# etap2.net
KiCad netlist of a schematic drawn in Altium Designer
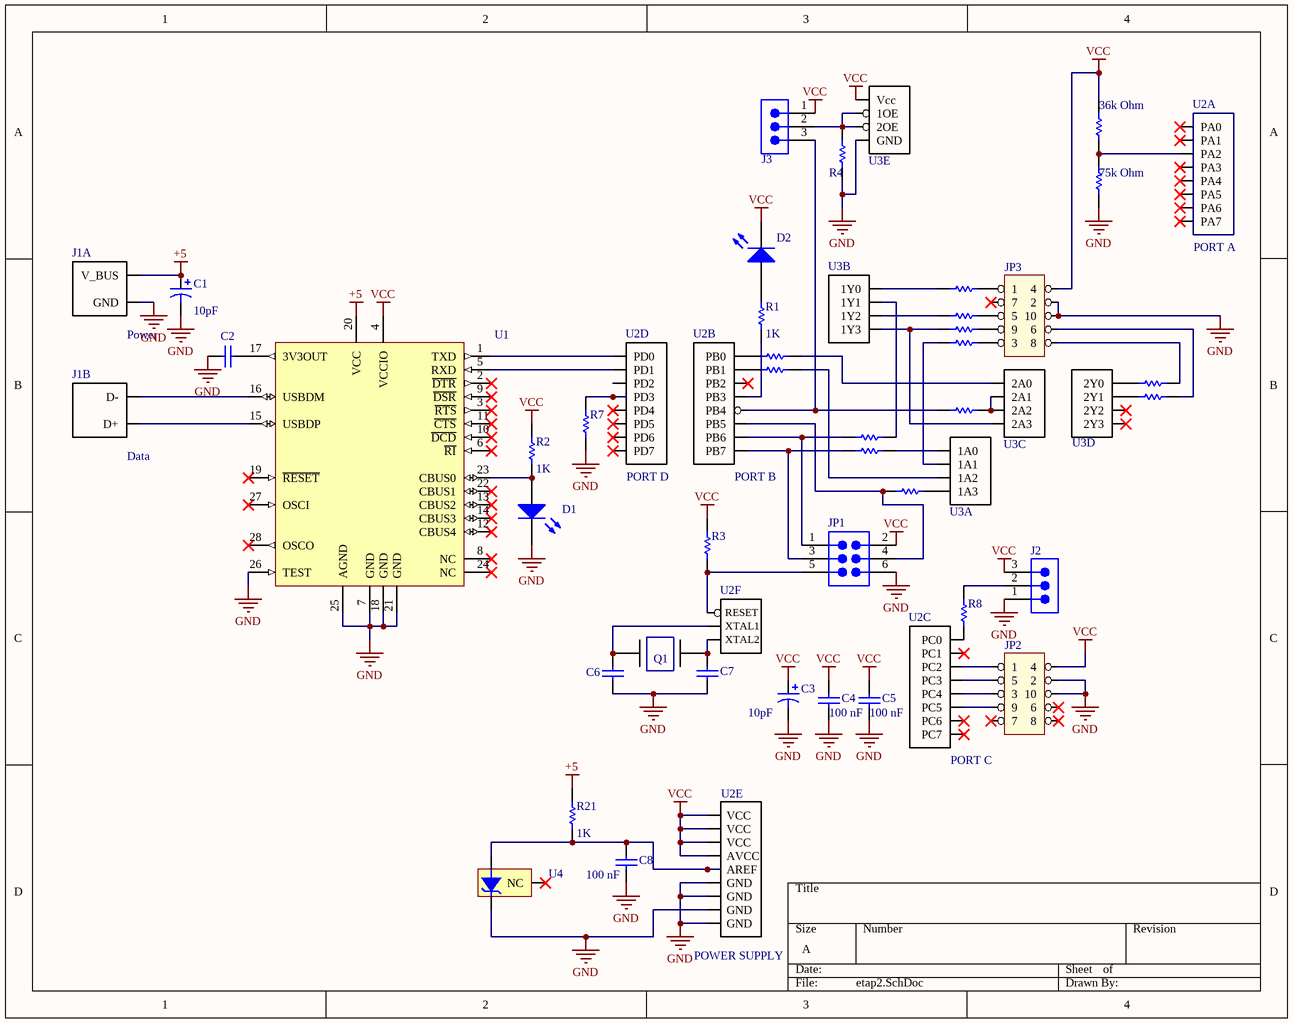
[diagram p0: etap2.SchDoc]

(export (version "E")
  (design (tool "Eeschema 10.0.6"))
  (components
    (comp (ref "C1")
      (value "10pF")
      (footprint "RB7.6-15")
      (description "Polarized Capacitor (Radial)")
      (fields (field (name "Comment") "Cap Pol1") (field (name "PUBLISHER") "Altium Limited"))
      (libsource (lib "Miscellaneous Devices") (part "Cap Pol1"))
    )
    (comp (ref "C2")
      (value "06035C104KAT2A")
      (footprint "CAPC1608X90X35LL15T15")
      (description "Chip Capacitor, 100 nF, +/- 10%, 50 V, -55 to 125 degC, 0603 (1608 Metric), RoHS, Tape and Reel")
      (fields (field (name "TOLERANCE") "10%"))
      (libsource (lib "Altium Content Vault") (part "CMP-2006-04389-2"))
    )
    (comp (ref "C3")
      (value "10pF")
      (footprint "RB7.6-15")
      (description "Polarized Capacitor (Radial)")
      (fields (field (name "Comment") "Cap Pol1") (field (name "PUBLISHER") "Altium Limited"))
      (libsource (lib "Miscellaneous Devices") (part "Cap Pol1"))
    )
    (comp (ref "C4")
      (value "06035C104KAT2A")
      (footprint "CAPC1608X90X35LL15T15")
      (description "Chip Capacitor, 100 nF, +/- 10%, 50 V, -55 to 125 degC, 0603 (1608 Metric), RoHS, Tape and Reel")
      (fields (field (name "CAPACITANCE") "100 nF") (field (name "TOLERANCE") "10%"))
      (libsource (lib "Altium Content Vault") (part "CMP-2006-04389-2"))
    )
    (comp (ref "C5")
      (value "06035C104KAT2A")
      (footprint "CAPC1608X90X35LL15T15")
      (description "Chip Capacitor, 100 nF, +/- 10%, 50 V, -55 to 125 degC, 0603 (1608 Metric), RoHS, Tape and Reel")
      (fields (field (name "CAPACITANCE") "100 nF") (field (name "TOLERANCE") "10%"))
      (libsource (lib "Altium Content Vault") (part "CMP-2006-04389-2"))
    )
    (comp (ref "C6")
      (value "CAP 22pF 50V 0402(1005)")
      (footprint "CAPC0402(1005)60_L")
      (description "CAP 22pF 50V ±0.5pF 0402 (1005 Metric) Thickness 0.6mm SMD")
      (fields (field (name "TOLERANCE") "Â±0.5pF"))
      (libsource (lib "Altium Content Vault") (part "CMP-1034-00913-1"))
    )
    (comp (ref "C7")
      (value "CAP 22pF 50V 0402(1005)")
      (footprint "CAPC0402(1005)60_L")
      (description "CAP 22pF 50V ±0.5pF 0402 (1005 Metric) Thickness 0.6mm SMD")
      (fields (field (name "TOLERANCE") "Â±0.5pF"))
      (libsource (lib "Altium Content Vault") (part "CMP-1034-00913-1"))
    )
    (comp (ref "C8")
      (value "06035C104KAT2A")
      (footprint "CAPC1608X90X35LL15T15")
      (description "Chip Capacitor, 100 nF, +/- 10%, 50 V, -55 to 125 degC, 0603 (1608 Metric), RoHS, Tape and Reel")
      (fields (field (name "CAPACITANCE") "100 nF") (field (name "TOLERANCE") "10%"))
      (libsource (lib "Altium Content Vault") (part "CMP-2006-04389-2"))
    )
    (comp (ref "D1")
      (value "151033YS03000")
      (footprint "Type 3mm")
      (description "THT LED round mono-color waterclear, WL-TMRW, Yellow")
      (fields (field (name "MANUFACTURER") "Wuerth Elektronik"))
      (libsource (lib "Altium Content Vault") (part "CMP-1489-00003-1"))
    )
    (comp (ref "D2")
      (value "151033GS03000")
      (footprint "Type 3mm")
      (description "THT LED round mono-color waterclear, THT WL-TMRW ,Green")
      (fields (field (name "MANUFACTURER") "Wuerth Elektronik"))
      (libsource (lib "Altium Content Vault") (part "CMP-1489-00001-1"))
    )
    (comp (ref "J1")
      (value "USB-B-S-X-X-TH")
      (footprint "USB_B")
      (description "USB-B interface")
      (libsource (lib "etap1") (part "USB-B-S-X-X-TH"))
    )
    (comp (ref "J2")
      (value "BG055-03-A-1-0650-0530-0350-L-B")
      (footprint "GCT-BG055-03-A-1-0650-0530-0350_V")
      (fields (field (name "MANUFACTURER") "GCT"))
      (libsource (lib "Altium Content Vault") (part "CMP-0815-00002-1"))
    )
    (comp (ref "J3")
      (value "BG055-03-A-1-0650-0530-0350-L-B")
      (footprint "GCT-BG055-03-A-1-0650-0530-0350_V")
      (fields (field (name "MANUFACTURER") "GCT"))
      (libsource (lib "") (part "CMP-0815-00002-1_1"))
    )
    (comp (ref "JP1")
      (value "TSW-103-08-G-D")
      (footprint "SMTC-TSW-103-08-X-D")
      (fields (field (name "MANUFACTURER") "Samtec"))
      (libsource (lib "Altium Content Vault") (part "CMP-1024-00338-1"))
    )
    (comp (ref "JP2") (value "IDC male 2.54 connector") (libsource (lib "etap1") (part "ZL231-10PG")))
    (comp (ref "JP3") (value "IDC male 2.54 connector") (libsource (lib "etap1") (part "ZL231-10GK")))
    (comp (ref "Q1") (value "XTAL") (libsource (lib "etap1") (part "HC49US-FF3F18")))
    (comp (ref "R1")
      (value "1K")
      (footprint "AXIAL-0.3")
      (description "Resistor")
      (fields (field (name "Comment") "Res1") (field (name "PUBLISHER") "Altium Limited"))
      (libsource (lib "Miscellaneous Devices") (part "Res1"))
    )
    (comp (ref "R2")
      (value "1K")
      (footprint "AXIAL-0.3")
      (description "Resistor")
      (fields (field (name "Comment") "Res1") (field (name "PUBLISHER") "Altium Limited"))
      (libsource (lib "Miscellaneous Devices") (part "Res1"))
    )
    (comp (ref "R3")
      (value "10K 1% 1812(4532)")
      (footprint "RESC1812(4532)_L")
      (description "10K 0.75W 1% 1812 (4532 Metric)  SMD")
      (fields (field (name "POWER") "0.75 W") (field (name "TOLERANCE") "1 %"))
      (libsource (lib "Altium Content Vault") (part "CMP-1016-00602-1"))
    )
    (comp (ref "R4")
      (value "10K 1% 1812(4532)")
      (footprint "RESC1812(4532)_L")
      (description "10K 0.75W 1% 1812 (4532 Metric)  SMD")
      (fields (field (name "POWER") "0.75 W") (field (name "TOLERANCE") "1 %"))
      (libsource (lib "Altium Content Vault") (part "CMP-1016-00602-1"))
    )
    (comp (ref "R5")
      (value "36k Ohm")
      (footprint "RESC0201(0603)_L")
      (description "36K 0.05W 5% 0201 (0603 Metric)  SMD")
      (fields (field (name "POWER") "0.05 W") (field (name "TOLERANCE") "5 %"))
      (libsource (lib "Altium Content Vault") (part "CMP-1010-00111-1"))
    )
    (comp (ref "R6")
      (value "75k Ohm")
      (footprint "RESC2010(5025)_M")
      (description "75K 0.75W 1% 2010 (5025 Metric)  SMD")
      (fields (field (name "TOLERANCE") "1 %") (field (name "POWER") "0.75 W"))
      (libsource (lib "Altium Content Vault") (part "CMP-1017-00722-1"))
    )
    (comp (ref "R7")
      (value "10K 1% 1812(4532)")
      (footprint "RESC1812(4532)_L")
      (description "10K 0.75W 1% 1812 (4532 Metric)  SMD")
      (fields (field (name "POWER") "0.75 W") (field (name "TOLERANCE") "1 %"))
      (libsource (lib "Altium Content Vault") (part "CMP-1016-00602-1"))
    )
    (comp (ref "R8")
      (value "Res1")
      (footprint "AXIAL-0.3")
      (description "Resistor")
      (fields (field (name "PUBLISHER") "Altium Limited"))
      (libsource (lib "Miscellaneous Devices") (part "Res1"))
    )
    (comp (ref "R9")
      (value "Res1")
      (footprint "AXIAL-0.3")
      (description "Resistor")
      (fields (field (name "PUBLISHER") "Altium Limited"))
      (libsource (lib "Miscellaneous Devices") (part "Res1"))
    )
    (comp (ref "R10")
      (value "Res1")
      (footprint "AXIAL-0.3")
      (description "Resistor")
      (fields (field (name "PUBLISHER") "Altium Limited"))
      (libsource (lib "Miscellaneous Devices") (part "Res1"))
    )
    (comp (ref "R11")
      (value "Res1")
      (footprint "AXIAL-0.3")
      (description "Resistor")
      (fields (field (name "PUBLISHER") "Altium Limited"))
      (libsource (lib "Miscellaneous Devices") (part "Res1"))
    )
    (comp (ref "R12")
      (value "Res1")
      (footprint "AXIAL-0.3")
      (description "Resistor")
      (fields (field (name "PUBLISHER") "Altium Limited"))
      (libsource (lib "Miscellaneous Devices") (part "Res1"))
    )
    (comp (ref "R13")
      (value "Res1")
      (footprint "AXIAL-0.3")
      (description "Resistor")
      (fields (field (name "PUBLISHER") "Altium Limited"))
      (libsource (lib "Miscellaneous Devices") (part "Res1"))
    )
    (comp (ref "R14")
      (value "Res1")
      (footprint "AXIAL-0.3")
      (description "Resistor")
      (fields (field (name "PUBLISHER") "Altium Limited"))
      (libsource (lib "Miscellaneous Devices") (part "Res1"))
    )
    (comp (ref "R15")
      (value "Res1")
      (footprint "AXIAL-0.3")
      (description "Resistor")
      (fields (field (name "PUBLISHER") "Altium Limited"))
      (libsource (lib "Miscellaneous Devices") (part "Res1"))
    )
    (comp (ref "R16")
      (value "100R 1% 2512(6432)")
      (footprint "RESC2512(6432)_N")
      (description "100R 1W 1% 2512 (6432 Metric)  SMD")
      (fields (field (name "POWER") "1 W") (field (name "TOLERANCE") "1 %"))
      (libsource (lib "Altium Content Vault") (part "CMP-1018-00397-1"))
    )
    (comp (ref "R17")
      (value "100R 1% 2512(6432)")
      (footprint "RESC2512(6432)_N")
      (description "100R 1W 1% 2512 (6432 Metric)  SMD")
      (fields (field (name "POWER") "1 W") (field (name "TOLERANCE") "1 %"))
      (libsource (lib "Altium Content Vault") (part "CMP-1018-00397-1"))
    )
    (comp (ref "R18")
      (value "100R 1% 2512(6432)")
      (footprint "RESC2512(6432)_N")
      (description "100R 1W 1% 2512 (6432 Metric)  SMD")
      (fields (field (name "POWER") "1 W") (field (name "TOLERANCE") "1 %"))
      (libsource (lib "Altium Content Vault") (part "CMP-1018-00397-1"))
    )
    (comp (ref "R19")
      (value "Res1")
      (footprint "AXIAL-0.3")
      (description "Resistor")
      (fields (field (name "PUBLISHER") "Altium Limited"))
      (libsource (lib "Miscellaneous Devices") (part "Res1"))
    )
    (comp (ref "R20")
      (value "Res1")
      (footprint "AXIAL-0.3")
      (description "Resistor")
      (fields (field (name "PUBLISHER") "Altium Limited"))
      (libsource (lib "Miscellaneous Devices") (part "Res1"))
    )
    (comp (ref "R21")
      (value "1K")
      (footprint "AXIAL-0.3")
      (description "Resistor")
      (fields (field (name "Comment") "Res1") (field (name "PUBLISHER") "Altium Limited"))
      (libsource (lib "Miscellaneous Devices") (part "Res1"))
    )
    (comp (ref "U1")
      (value "FT232RL-Reel")
      (footprint "SSOP-28_L")
      (description "USB UART Asynchronous Serial Data Transfer Chip, 28-pin SSOP, Tape and Reel")
      (fields (field (name "MANUFACTURER") "FTDI"))
      (libsource (lib "Altium Content Vault") (part "CMP-0078-00029-3"))
    )
    (comp (ref "U2")
      (value "Microcontroller")
      (footprint "TQFP44")
      (description "Microcontroller with 16k bytes in-system programmable flash")
      (libsource (lib "etap1") (part "Atmega16-16AU"))
    )
    (comp (ref "U3") (value "Octal buffer-line driver") (libsource (lib "etap1") (part "74HC2444N")))
    (comp (ref "U4")
      (value "LM385BYZ-2.5")
      (footprint "Z03A")
      (description "Micropower Voltage Reference Diode, 3-pin TO-92")
      (fields (field (name "MANUFACTURER") "National Semiconductor"))
      (libsource (lib "Altium Content Vault") (part "CMP-0074-00031-2"))
    )
  )
  (nets
    (net (code "1") (name "+5") (class "Default")
      (node (ref "C1") (pin "1") (pinfunction "1_1") (pintype "passive"))
      (node (ref "J1") (pin "1") (pinfunction "V_BUS_1") (pintype "passive"))
      (node (ref "R21") (pin "2") (pinfunction "2_2") (pintype "passive"))
      (node (ref "U1") (pin "20") (pinfunction "VCC_20") (pintype "power_in"))
    )
    (net (code "2") (name "GND") (class "Default")
      (node (ref "C1") (pin "2") (pinfunction "2_2") (pintype "passive"))
      (node (ref "C2") (pin "2") (pinfunction "2_2") (pintype "passive"))
      (node (ref "C3") (pin "2") (pinfunction "2_2") (pintype "passive"))
      (node (ref "C4") (pin "1") (pinfunction "1_1") (pintype "passive"))
      (node (ref "C5") (pin "1") (pinfunction "1_1") (pintype "passive"))
      (node (ref "C6") (pin "1") (pinfunction "1_1") (pintype "passive"))
      (node (ref "C7") (pin "1") (pinfunction "1_1") (pintype "passive"))
      (node (ref "C8") (pin "1") (pinfunction "1_1") (pintype "passive"))
      (node (ref "D1") (pin "1") (pinfunction "K_1") (pintype "passive"))
      (node (ref "J1") (pin "4") (pinfunction "GND_4") (pintype "passive"))
      (node (ref "J2") (pin "1") (pinfunction "1_1") (pintype "passive"))
      (node (ref "JP1") (pin "6") (pinfunction "6_6") (pintype "passive"))
      (node (ref "JP2") (pin "10") (pinfunction "10_10") (pintype "passive"))
      (node (ref "JP2") (pin "2") (pinfunction "2_2") (pintype "passive"))
      (node (ref "JP3") (pin "10") (pinfunction "10_10") (pintype "passive"))
      (node (ref "JP3") (pin "2") (pinfunction "2_2") (pintype "passive"))
      (node (ref "R4") (pin "1") (pinfunction "1_1") (pintype "passive"))
      (node (ref "R6") (pin "1") (pinfunction "1_1") (pintype "passive"))
      (node (ref "R7") (pin "1") (pinfunction "1_1") (pintype "passive"))
      (node (ref "U1") (pin "18") (pinfunction "GND_18") (pintype "power_in"))
      (node (ref "U1") (pin "21") (pinfunction "GND_21") (pintype "power_in"))
      (node (ref "U1") (pin "25") (pinfunction "AGND_25") (pintype "power_in"))
      (node (ref "U1") (pin "26") (pinfunction "TEST_26") (pintype "input"))
      (node (ref "U1") (pin "7") (pinfunction "GND_7") (pintype "power_in"))
      (node (ref "U2") (pin "18") (pinfunction "GND_18") (pintype "passive"))
      (node (ref "U2") (pin "28") (pinfunction "GND_28") (pintype "passive"))
      (node (ref "U2") (pin "39") (pinfunction "GND_39") (pintype "passive"))
      (node (ref "U2") (pin "6") (pinfunction "GND_6") (pintype "passive"))
      (node (ref "U3") (pin "10") (pinfunction "GND_10") (pintype "passive"))
      (node (ref "U4") (pin "2") (pinfunction "+V_2") (pintype "passive"))
    )
    (net (code "3") (name "Net-(D1-A)") (class "Default")
      (node (ref "D1") (pin "2") (pinfunction "A_2") (pintype "passive"))
      (node (ref "R2") (pin "1") (pinfunction "1_1") (pintype "passive"))
      (node (ref "U1") (pin "23") (pinfunction "CBUS0_23") (pintype "bidirectional"))
    )
    (net (code "4") (name "Net-(D2-A)") (class "Default")
      (node (ref "D2") (pin "2") (pinfunction "A_2") (pintype "passive"))
      (node (ref "R1") (pin "2") (pinfunction "2_2") (pintype "passive"))
    )
    (net (code "5") (name "Net-(J1B-D+)") (class "Default")
      (node (ref "J1") (pin "3") (pinfunction "D+_3") (pintype "passive"))
      (node (ref "U1") (pin "15") (pinfunction "USBDP_15") (pintype "bidirectional"))
    )
    (net (code "6") (name "Net-(J1B-D-)") (class "Default")
      (node (ref "J1") (pin "2") (pinfunction "D-_2") (pintype "passive"))
      (node (ref "U1") (pin "16") (pinfunction "USBDM_16") (pintype "bidirectional"))
    )
    (net (code "7") (name "Net-(J2-Pad2)") (class "Default")
      (node (ref "J2") (pin "2") (pinfunction "2_2") (pintype "passive"))
      (node (ref "R8") (pin "2") (pinfunction "2_2") (pintype "passive"))
    )
    (net (code "8") (name "Net-(JP3-Pad1)") (class "Default")
      (node (ref "JP3") (pin "1") (pinfunction "1_1") (pintype "passive"))
      (node (ref "R16") (pin "2") (pinfunction "2_2") (pintype "passive"))
    )
    (net (code "9") (name "Net-(JP3-Pad3)") (class "Default")
      (node (ref "JP3") (pin "3") (pinfunction "3_3") (pintype "passive"))
      (node (ref "R15") (pin "1") (pinfunction "1_1") (pintype "passive"))
    )
    (net (code "10") (name "Net-(JP3-Pad5)") (class "Default")
      (node (ref "JP3") (pin "5") (pinfunction "5_5") (pintype "passive"))
      (node (ref "R17") (pin "2") (pinfunction "2_2") (pintype "passive"))
    )
    (net (code "11") (name "Net-(JP3-Pad6)") (class "Default")
      (node (ref "JP3") (pin "6") (pinfunction "6_6") (pintype "passive"))
      (node (ref "R20") (pin "1") (pinfunction "1_1") (pintype "passive"))
    )
    (net (code "12") (name "Net-(JP3-Pad8)") (class "Default")
      (node (ref "JP3") (pin "8") (pinfunction "8_8") (pintype "passive"))
      (node (ref "R19") (pin "2") (pinfunction "2_2") (pintype "passive"))
    )
    (net (code "13") (name "Net-(JP3-Pad9)") (class "Default")
      (node (ref "JP3") (pin "9") (pinfunction "9_9") (pintype "passive"))
      (node (ref "R18") (pin "2") (pinfunction "2_2") (pintype "passive"))
    )
    (net (code "14") (name "Net-(U1-3V3OUT)") (class "Default")
      (node (ref "C2") (pin "1") (pinfunction "1_1") (pintype "passive"))
      (node (ref "U1") (pin "17") (pinfunction "3V3OUT_17") (pintype "output"))
    )
    (net (code "15") (name "Net-(U1-RXD)") (class "Default")
      (node (ref "U1") (pin "5") (pinfunction "RXD_5") (pintype "input"))
      (node (ref "U2") (pin "10") (pinfunction "PD1_10") (pintype "passive"))
    )
    (net (code "16") (name "Net-(U1-TXD)") (class "Default")
      (node (ref "U1") (pin "1") (pinfunction "TXD_1") (pintype "output"))
      (node (ref "U2") (pin "9") (pinfunction "PD0_9") (pintype "passive"))
    )
    (net (code "17") (name "Net-(U2A-PA2)") (class "Default")
      (node (ref "R5") (pin "1") (pinfunction "1_1") (pintype "passive"))
      (node (ref "R6") (pin "2") (pinfunction "2_2") (pintype "passive"))
      (node (ref "U2") (pin "35") (pinfunction "PA2_35") (pintype "passive"))
    )
    (net (code "18") (name "Net-(U2B-PB0)") (class "Default")
      (node (ref "R13") (pin "2") (pinfunction "2_2") (pintype "passive"))
      (node (ref "U2") (pin "40") (pinfunction "PB0_40") (pintype "passive"))
    )
    (net (code "19") (name "Net-(U2B-PB1)") (class "Default")
      (node (ref "R11") (pin "2") (pinfunction "2_2") (pintype "passive"))
      (node (ref "U2") (pin "41") (pinfunction "PB1_41") (pintype "passive"))
    )
    (net (code "20") (name "Net-(U2B-PB3)") (class "Default")
      (node (ref "R1") (pin "1") (pinfunction "1_1") (pintype "passive"))
      (node (ref "U2") (pin "43") (pinfunction "PB3_43") (pintype "passive"))
    )
    (net (code "21") (name "Net-(U2B-PB4)") (class "Default")
      (node (ref "J3") (pin "3") (pinfunction "3_3") (pintype "passive"))
      (node (ref "R14") (pin "2") (pinfunction "2_2") (pintype "passive"))
      (node (ref "U2") (pin "44") (pinfunction "PB4_44") (pintype "passive"))
    )
    (net (code "22") (name "Net-(U2B-PB5)") (class "Default")
      (node (ref "JP1") (pin "4") (pinfunction "4_4") (pintype "passive"))
      (node (ref "R12") (pin "2") (pinfunction "2_2") (pintype "passive"))
      (node (ref "U2") (pin "1") (pinfunction "PB5_1") (pintype "passive"))
    )
    (net (code "23") (name "Net-(U2B-PB6)") (class "Default")
      (node (ref "JP1") (pin "1") (pinfunction "1_1") (pintype "passive"))
      (node (ref "R9") (pin "2") (pinfunction "2_2") (pintype "passive"))
      (node (ref "U2") (pin "2") (pinfunction "PB6_2") (pintype "passive"))
    )
    (net (code "24") (name "Net-(U2B-PB7)") (class "Default")
      (node (ref "JP1") (pin "3") (pinfunction "3_3") (pintype "passive"))
      (node (ref "R10") (pin "2") (pinfunction "2_2") (pintype "passive"))
      (node (ref "U2") (pin "3") (pinfunction "PB7_3") (pintype "passive"))
    )
    (net (code "25") (name "Net-(U2C-PC0)") (class "Default")
      (node (ref "R8") (pin "1") (pinfunction "1_1") (pintype "passive"))
      (node (ref "U2") (pin "19") (pinfunction "PC0_19") (pintype "passive"))
    )
    (net (code "26") (name "Net-(U2C-PC2)") (class "Default")
      (node (ref "JP2") (pin "1") (pinfunction "1_1") (pintype "passive"))
      (node (ref "U2") (pin "21") (pinfunction "PC2_21") (pintype "passive"))
    )
    (net (code "27") (name "Net-(U2C-PC3)") (class "Default")
      (node (ref "JP2") (pin "5") (pinfunction "5_5") (pintype "passive"))
      (node (ref "U2") (pin "22") (pinfunction "PC3_22") (pintype "passive"))
    )
    (net (code "28") (name "Net-(U2C-PC4)") (class "Default")
      (node (ref "JP2") (pin "3") (pinfunction "3_3") (pintype "passive"))
      (node (ref "U2") (pin "23") (pinfunction "PC4_23") (pintype "passive"))
    )
    (net (code "29") (name "Net-(U2C-PC5)") (class "Default")
      (node (ref "JP2") (pin "9") (pinfunction "9_9") (pintype "passive"))
      (node (ref "U2") (pin "24") (pinfunction "PC5_24") (pintype "passive"))
    )
    (net (code "30") (name "Net-(U2D-PD3)") (class "Default")
      (node (ref "R7") (pin "2") (pinfunction "2_2") (pintype "passive"))
      (node (ref "U2") (pin "12") (pinfunction "PD3_12") (pintype "passive"))
    )
    (net (code "31") (name "Net-(U2E-AREF)") (class "Default")
      (node (ref "C8") (pin "2") (pinfunction "2_2") (pintype "passive"))
      (node (ref "R21") (pin "1") (pinfunction "1_1") (pintype "passive"))
      (node (ref "U2") (pin "29") (pinfunction "AREF_29") (pintype "passive"))
      (node (ref "U4") (pin "3") (pinfunction "-V_3") (pintype "passive"))
    )
    (net (code "32") (name "Net-(U2F-RESET)") (class "Default")
      (node (ref "JP1") (pin "5") (pinfunction "5_5") (pintype "passive"))
      (node (ref "R3") (pin "1") (pinfunction "1_1") (pintype "passive"))
      (node (ref "U2") (pin "4") (pinfunction "RESET_4") (pintype "passive"))
    )
    (net (code "33") (name "Net-(U2F-XTAL1)") (class "Default")
      (node (ref "C6") (pin "2") (pinfunction "2_2") (pintype "passive"))
      (node (ref "Q1") (pin "1") (pinfunction "1_1") (pintype "passive"))
      (node (ref "U2") (pin "8") (pinfunction "XTAL1_8") (pintype "passive"))
    )
    (net (code "34") (name "Net-(U2F-XTAL2)") (class "Default")
      (node (ref "C7") (pin "2") (pinfunction "2_2") (pintype "passive"))
      (node (ref "Q1") (pin "2") (pinfunction "2_2") (pintype "passive"))
      (node (ref "U2") (pin "7") (pinfunction "XTAL2_7") (pintype "passive"))
    )
    (net (code "35") (name "Net-(U3A-1A0)") (class "Default")
      (node (ref "R10") (pin "1") (pinfunction "1_1") (pintype "passive"))
      (node (ref "U3") (pin "2") (pinfunction "1A0_2") (pintype "passive"))
    )
    (net (code "36") (name "Net-(U3A-1A1)") (class "Default")
      (node (ref "R15") (pin "2") (pinfunction "2_2") (pintype "passive"))
      (node (ref "U3") (pin "4") (pinfunction "1A1_4") (pintype "passive"))
    )
    (net (code "37") (name "Net-(U3A-1A2)") (class "Default")
      (node (ref "R11") (pin "1") (pinfunction "1_1") (pintype "passive"))
      (node (ref "U3") (pin "6") (pinfunction "1A2_6") (pintype "passive"))
    )
    (net (code "38") (name "Net-(U3A-1A3)") (class "Default")
      (node (ref "R12") (pin "1") (pinfunction "1_1") (pintype "passive"))
      (node (ref "U3") (pin "8") (pinfunction "1A3_8") (pintype "passive"))
    )
    (net (code "39") (name "Net-(U3B-1Y0)") (class "Default")
      (node (ref "R16") (pin "1") (pinfunction "1_1") (pintype "passive"))
      (node (ref "U3") (pin "18") (pinfunction "1Y0_18") (pintype "passive"))
    )
    (net (code "40") (name "Net-(U3B-1Y1)") (class "Default")
      (node (ref "R9") (pin "1") (pinfunction "1_1") (pintype "passive"))
      (node (ref "U3") (pin "16") (pinfunction "1Y1_16") (pintype "passive"))
    )
    (net (code "41") (name "Net-(U3B-1Y2)") (class "Default")
      (node (ref "R17") (pin "1") (pinfunction "1_1") (pintype "passive"))
      (node (ref "U3") (pin "14") (pinfunction "1Y2_14") (pintype "passive"))
    )
    (net (code "42") (name "Net-(U3B-1Y3)") (class "Default")
      (node (ref "R18") (pin "1") (pinfunction "1_1") (pintype "passive"))
      (node (ref "U3") (pin "11") (pinfunction "2A3_11") (pintype "passive"))
      (node (ref "U3") (pin "12") (pinfunction "1Y3_12") (pintype "passive"))
    )
    (net (code "43") (name "Net-(U3C-2A0)") (class "Default")
      (node (ref "R13") (pin "1") (pinfunction "1_1") (pintype "passive"))
      (node (ref "U3") (pin "17") (pinfunction "2A0_17") (pintype "passive"))
    )
    (net (code "44") (name "Net-(U3C-2A1)") (class "Default")
      (node (ref "R14") (pin "1") (pinfunction "1_1") (pintype "passive"))
      (node (ref "U3") (pin "13") (pinfunction "2A2_13") (pintype "passive"))
      (node (ref "U3") (pin "15") (pinfunction "2A1_15") (pintype "passive"))
    )
    (net (code "45") (name "Net-(U3D-2Y0)") (class "Default")
      (node (ref "R19") (pin "1") (pinfunction "1_1") (pintype "passive"))
      (node (ref "U3") (pin "3") (pinfunction "2Y0_3") (pintype "passive"))
    )
    (net (code "46") (name "Net-(U3D-2Y1)") (class "Default")
      (node (ref "R20") (pin "2") (pinfunction "2_2") (pintype "passive"))
      (node (ref "U3") (pin "5") (pinfunction "2Y1_5") (pintype "passive"))
    )
    (net (code "47") (name "Net-(U3E-1OE)") (class "Default")
      (node (ref "J3") (pin "2") (pinfunction "2_2") (pintype "passive"))
      (node (ref "R4") (pin "2") (pinfunction "2_2") (pintype "passive"))
      (node (ref "U3") (pin "1") (pinfunction "1OE_1") (pintype "passive"))
      (node (ref "U3") (pin "19") (pinfunction "2OE_19") (pintype "passive"))
    )
    (net (code "48") (name "VCC") (class "Default")
      (node (ref "C3") (pin "1") (pinfunction "1_1") (pintype "passive"))
      (node (ref "C4") (pin "2") (pinfunction "2_2") (pintype "passive"))
      (node (ref "C5") (pin "2") (pinfunction "2_2") (pintype "passive"))
      (node (ref "D2") (pin "1") (pinfunction "K_1") (pintype "passive"))
      (node (ref "J2") (pin "3") (pinfunction "3_3") (pintype "passive"))
      (node (ref "J3") (pin "1") (pinfunction "1_1") (pintype "passive"))
      (node (ref "JP1") (pin "2") (pinfunction "2_2") (pintype "passive"))
      (node (ref "JP2") (pin "4") (pinfunction "4_4") (pintype "passive"))
      (node (ref "JP3") (pin "4") (pinfunction "4_4") (pintype "passive"))
      (node (ref "R2") (pin "2") (pinfunction "2_2") (pintype "passive"))
      (node (ref "R3") (pin "2") (pinfunction "2_2") (pintype "passive"))
      (node (ref "R5") (pin "2") (pinfunction "2_2") (pintype "passive"))
      (node (ref "U1") (pin "4") (pinfunction "VCCIO_4") (pintype "power_in"))
      (node (ref "U2") (pin "17") (pinfunction "VCC_17") (pintype "passive"))
      (node (ref "U2") (pin "27") (pinfunction "AVCC_27") (pintype "passive"))
      (node (ref "U2") (pin "38") (pinfunction "VCC_38") (pintype "passive"))
      (node (ref "U2") (pin "5") (pinfunction "VCC_5") (pintype "passive"))
      (node (ref "U3") (pin "20") (pinfunction "Vcc_20") (pintype "passive"))
    )
    (net (code "49") (name "unconnected-(JP2-Pad6)") (class "Default")
      (node (ref "JP2") (pin "6") (pinfunction "6_6") (pintype "passive+no_connect"))
    )
    (net (code "50") (name "unconnected-(JP2-Pad7)") (class "Default")
      (node (ref "JP2") (pin "7") (pinfunction "7_7") (pintype "passive+no_connect"))
    )
    (net (code "51") (name "unconnected-(JP2-Pad8)") (class "Default")
      (node (ref "JP2") (pin "8") (pinfunction "8_8") (pintype "passive+no_connect"))
    )
    (net (code "52") (name "unconnected-(JP3-Pad7)") (class "Default")
      (node (ref "JP3") (pin "7") (pinfunction "7_7") (pintype "passive+no_connect"))
    )
    (net (code "53") (name "unconnected-(U1-CBUS1-Pad22)") (class "Default")
      (node (ref "U1") (pin "22") (pinfunction "CBUS1_22") (pintype "bidirectional+no_connect"))
    )
    (net (code "54") (name "unconnected-(U1-CBUS2-Pad13)") (class "Default")
      (node (ref "U1") (pin "13") (pinfunction "CBUS2_13") (pintype "bidirectional+no_connect"))
    )
    (net (code "55") (name "unconnected-(U1-CBUS3-Pad14)") (class "Default")
      (node (ref "U1") (pin "14") (pinfunction "CBUS3_14") (pintype "bidirectional+no_connect"))
    )
    (net (code "56") (name "unconnected-(U1-CBUS4-Pad12)") (class "Default")
      (node (ref "U1") (pin "12") (pinfunction "CBUS4_12") (pintype "bidirectional+no_connect"))
    )
    (net (code "57") (name "unconnected-(U1-NC-Pad8)") (class "Default")
      (node (ref "U1") (pin "8") (pinfunction "NC_8") (pintype "passive+no_connect"))
    )
    (net (code "58") (name "unconnected-(U1-NC-Pad24)") (class "Default")
      (node (ref "U1") (pin "24") (pinfunction "NC_24") (pintype "passive+no_connect"))
    )
    (net (code "59") (name "unconnected-(U1-OSCI-Pad27)") (class "Default")
      (node (ref "U1") (pin "27") (pinfunction "OSCI_27") (pintype "input+no_connect"))
    )
    (net (code "60") (name "unconnected-(U1-OSCO-Pad28)") (class "Default")
      (node (ref "U1") (pin "28") (pinfunction "OSCO_28") (pintype "output+no_connect"))
    )
    (net (code "61") (name "unconnected-(U1-~{CTS}-Pad11)") (class "Default")
      (node (ref "U1") (pin "11") (pinfunction "~{CTS}_11") (pintype "input+no_connect"))
    )
    (net (code "62") (name "unconnected-(U1-~{DCD}-Pad10)") (class "Default")
      (node (ref "U1") (pin "10") (pinfunction "~{DCD}_10") (pintype "input+no_connect"))
    )
    (net (code "63") (name "unconnected-(U1-~{DSR}-Pad9)") (class "Default")
      (node (ref "U1") (pin "9") (pinfunction "~{DSR}_9") (pintype "input+no_connect"))
    )
    (net (code "64") (name "unconnected-(U1-~{DTR}-Pad2)") (class "Default")
      (node (ref "U1") (pin "2") (pinfunction "~{DTR}_2") (pintype "output+no_connect"))
    )
    (net (code "65") (name "unconnected-(U1-~{RESET}-Pad19)") (class "Default")
      (node (ref "U1") (pin "19") (pinfunction "~{RESET}_19") (pintype "input+no_connect"))
    )
    (net (code "66") (name "unconnected-(U1-~{RI}-Pad6)") (class "Default")
      (node (ref "U1") (pin "6") (pinfunction "~{RI}_6") (pintype "input+no_connect"))
    )
    (net (code "67") (name "unconnected-(U1-~{RTS}-Pad3)") (class "Default")
      (node (ref "U1") (pin "3") (pinfunction "~{RTS}_3") (pintype "output+no_connect"))
    )
    (net (code "68") (name "unconnected-(U2A-PA0-Pad37)") (class "Default")
      (node (ref "U2") (pin "37") (pinfunction "PA0_37") (pintype "passive+no_connect"))
    )
    (net (code "69") (name "unconnected-(U2A-PA1-Pad36)") (class "Default")
      (node (ref "U2") (pin "36") (pinfunction "PA1_36") (pintype "passive+no_connect"))
    )
    (net (code "70") (name "unconnected-(U2A-PA3-Pad34)") (class "Default")
      (node (ref "U2") (pin "34") (pinfunction "PA3_34") (pintype "passive+no_connect"))
    )
    (net (code "71") (name "unconnected-(U2A-PA4-Pad33)") (class "Default")
      (node (ref "U2") (pin "33") (pinfunction "PA4_33") (pintype "passive+no_connect"))
    )
    (net (code "72") (name "unconnected-(U2A-PA5-Pad32)") (class "Default")
      (node (ref "U2") (pin "32") (pinfunction "PA5_32") (pintype "passive+no_connect"))
    )
    (net (code "73") (name "unconnected-(U2A-PA6-Pad31)") (class "Default")
      (node (ref "U2") (pin "31") (pinfunction "PA6_31") (pintype "passive+no_connect"))
    )
    (net (code "74") (name "unconnected-(U2A-PA7-Pad30)") (class "Default")
      (node (ref "U2") (pin "30") (pinfunction "PA7_30") (pintype "passive+no_connect"))
    )
    (net (code "75") (name "unconnected-(U2B-PB2-Pad42)") (class "Default")
      (node (ref "U2") (pin "42") (pinfunction "PB2_42") (pintype "passive+no_connect"))
    )
    (net (code "76") (name "unconnected-(U2C-PC1-Pad20)") (class "Default")
      (node (ref "U2") (pin "20") (pinfunction "PC1_20") (pintype "passive+no_connect"))
    )
    (net (code "77") (name "unconnected-(U2C-PC6-Pad25)") (class "Default")
      (node (ref "U2") (pin "25") (pinfunction "PC6_25") (pintype "passive+no_connect"))
    )
    (net (code "78") (name "unconnected-(U2C-PC7-Pad26)") (class "Default")
      (node (ref "U2") (pin "26") (pinfunction "PC7_26") (pintype "passive+no_connect"))
    )
    (net (code "79") (name "unconnected-(U2D-PD2-Pad11)") (class "Default")
      (node (ref "U2") (pin "11") (pinfunction "PD2_11") (pintype "passive"))
    )
    (net (code "80") (name "unconnected-(U2D-PD4-Pad13)") (class "Default")
      (node (ref "U2") (pin "13") (pinfunction "PD4_13") (pintype "passive+no_connect"))
    )
    (net (code "81") (name "unconnected-(U2D-PD5-Pad14)") (class "Default")
      (node (ref "U2") (pin "14") (pinfunction "PD5_14") (pintype "passive+no_connect"))
    )
    (net (code "82") (name "unconnected-(U2D-PD6-Pad15)") (class "Default")
      (node (ref "U2") (pin "15") (pinfunction "PD6_15") (pintype "passive+no_connect"))
    )
    (net (code "83") (name "unconnected-(U2D-PD7-Pad16)") (class "Default")
      (node (ref "U2") (pin "16") (pinfunction "PD7_16") (pintype "passive+no_connect"))
    )
    (net (code "84") (name "unconnected-(U3D-2Y2-Pad7)") (class "Default")
      (node (ref "U3") (pin "7") (pinfunction "2Y2_7") (pintype "passive+no_connect"))
    )
    (net (code "85") (name "unconnected-(U3D-2Y3-Pad9)") (class "Default")
      (node (ref "U3") (pin "9") (pinfunction "2Y3_9") (pintype "passive+no_connect"))
    )
    (net (code "86") (name "unconnected-(U4-NC-Pad1)") (class "Default")
      (node (ref "U4") (pin "1") (pinfunction "NC_1") (pintype "passive+no_connect"))
    )
  )
)
